# Circuit_primaire.net
KiCad netlist of a schematic drawn in Altium Designer
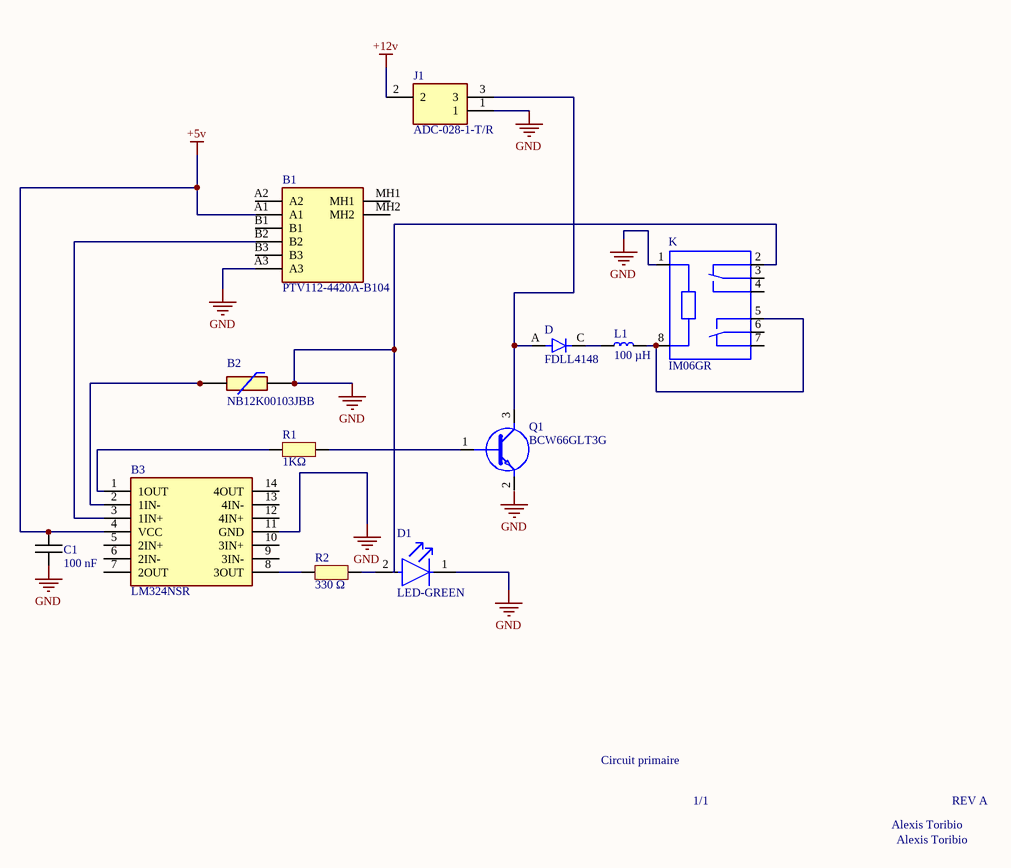
[diagram p0: Circuit primaire.SchDoc]

(export (version "E")
  (design (tool "Eeschema 10.0.6"))
  (components
    (comp (ref "B1")
      (value "PTV112-4420A-B104")
      (footprint "PTV1124420AB104")
      (description "Potentiometers PANEL CONTROL 100kOhm")
      (fields (field (name "MOUSER PART NUMBER") "652-PTV1124420AB104"))
      (libsource (lib "Schlib1") (part "PTV112-4420A-B104"))
    )
    (comp (ref "B2")
      (value "NB12K00103JBB")
      (footprint "RESC2212X50N")
      (description "NTC SMD Thermistor, NB12K, 10K, 5% AVX 10k 0805 Protection NTC Thermistor, 5s, 2 x 1.25 x 1.3mm")
      (fields (field (name "MOUSER PART NUMBER") "581-NB12K00103JBB"))
      (libsource (lib "Schlib1") (part "NB12K00103JBB"))
    )
    (comp (ref "B3")
      (value "LM324NSR")
      (footprint "SOIC127P780X200-14N")
      (description "Quadruple Operational Amplifier")
      (fields (field (name "MOUSER PART NUMBER") "595-LM324NSR"))
      (libsource (lib "Schlib1") (part "LM324NSR"))
    )
    (comp (ref "C1")
      (value "100 nF")
      (footprint "CAPC1005X06N")
      (libsource (lib "Schlib1") (part "Capacitor"))
    )
    (comp (ref "D")
      (value "FDLL4148")
      (footprint "DIOMELF3414N")
      (description "Diode Standard 100V 200mA Surface Mount SOD-80")
      (fields (field (name "MF") "ON Semiconductor") (field (name "DIGI-KEY_PART_NUMBER") "FDLL4148CT-ND"))
      (libsource (lib "Schlib1") (part "FDLL4148"))
    )
    (comp (ref "D1")
      (value "LED-GREEN")
      (footprint "SMD-1608-LED")
      (description "LED GREEN CLEAR CHIP SMD LTST-C190GKT")
      (fields (field (name "VOLTAGE") "2V"))
      (libsource (lib "Schlib1") (part "LED-GREEN"))
    )
    (comp (ref "J1")
      (value "ADC-028-1-T/R")
      (footprint "PJ1021SMTTR")
      (description "Connecteurs d'alimentation continue DC POWER JACK 2MM PIN TYPE 028")
      (fields (field (name "MOUSER PART NUMBER") "737-ADC-028-1-T/R"))
      (libsource (lib "Schlib1") (part "ADC-028-1-T/R"))
    )
    (comp (ref "K")
      (value "IM06GR")
      (footprint "RELAY_IM06GR")
      (description "Electromechanical Relay 12VDC 1.029KOhm 2A DPDT _10x7.5x5.65_mm SMD Signal Relay")
      (fields (field (name "MF") "TE Connectivity"))
      (libsource (lib "Schlib1") (part "IM06GR"))
    )
    (comp (ref "L1") (value "100 µH") (footprint "LQPC1005X06N") (libsource (lib "Schlib1") (part "Bobine")))
    (comp (ref "Q1")
      (value "BCW66GLT3G")
      (footprint "SOT96P237X111-3N")
      (description "NPN Bipolar Transistor")
      (fields (field (name "MOUSER PART NUMBER") "863-BCW66GLT3G"))
      (libsource (lib "Schlib1") (part "BCW66GLT3G"))
    )
    (comp (ref "R1") (value "1KΩ") (footprint "RESC1005X06N") (libsource (lib "Schlib1") (part "Resistor")))
    (comp (ref "R2") (value "330 Ω") (footprint "RESC1005X06N") (libsource (lib "Schlib1") (part "Resistor")))
  )
  (nets
    (net (code "1") (name "+5v") (class "Default")
      (node (ref "B1") (pin "A1") (pinfunction "A1_A1") (pintype "passive"))
      (node (ref "B3") (pin "4") (pinfunction "VCC_4") (pintype "passive"))
      (node (ref "C1") (pin "2") (pinfunction "2_2") (pintype "passive"))
    )
    (net (code "2") (name "+12v") (class "Default")
      (node (ref "J1") (pin "2") (pinfunction "2_2") (pintype "passive"))
    )
    (net (code "3") (name "GND") (class "Default")
      (node (ref "B1") (pin "A3") (pinfunction "A3_A3") (pintype "passive"))
      (node (ref "B2") (pin "1") (pinfunction "1_1") (pintype "passive"))
      (node (ref "B3") (pin "11") (pinfunction "GND_11") (pintype "passive"))
      (node (ref "C1") (pin "1") (pinfunction "1_1") (pintype "passive"))
      (node (ref "D1") (pin "1") (pinfunction "C_1") (pintype "passive"))
      (node (ref "J1") (pin "1") (pinfunction "1_1") (pintype "passive"))
      (node (ref "K") (pin "1") (pinfunction "1_1") (pintype "passive"))
      (node (ref "K") (pin "2") (pinfunction "2_2") (pintype "passive"))
    )
    (net (code "4") (name "Net-(B3-1IN+)") (class "Default")
      (node (ref "B1") (pin "B2") (pinfunction "B2_B2") (pintype "passive"))
      (node (ref "B3") (pin "3") (pinfunction "1IN+_3") (pintype "passive"))
    )
    (net (code "5") (name "Net-(B3-1IN-)") (class "Default")
      (node (ref "B2") (pin "2") (pinfunction "2_2") (pintype "passive"))
      (node (ref "B3") (pin "2") (pinfunction "1IN-_2") (pintype "passive"))
    )
    (net (code "6") (name "Net-(B3-1OUT)") (class "Default")
      (node (ref "B3") (pin "1") (pinfunction "1OUT_1") (pintype "passive"))
      (node (ref "R1") (pin "1") (pinfunction "1_1") (pintype "passive"))
    )
    (net (code "7") (name "Net-(B3-3OUT)") (class "Default")
      (node (ref "B3") (pin "8") (pinfunction "3OUT_8") (pintype "passive"))
      (node (ref "R2") (pin "1") (pinfunction "1_1") (pintype "passive"))
    )
    (net (code "8") (name "Net-(D-PadC)") (class "Default")
      (node (ref "D") (pin "C") (pinfunction "C_C") (pintype "passive"))
      (node (ref "L1") (pin "1") (pinfunction "1_1") (pintype "passive"))
    )
    (net (code "9") (name "Net-(D1-A)") (class "Default")
      (node (ref "D1") (pin "2") (pinfunction "A_2") (pintype "passive"))
      (node (ref "R2") (pin "2") (pinfunction "2_2") (pintype "passive"))
    )
    (net (code "10") (name "Net-(K-Pad5)") (class "Default")
      (node (ref "K") (pin "5") (pinfunction "5_5") (pintype "passive"))
      (node (ref "K") (pin "8") (pinfunction "8_8") (pintype "passive"))
      (node (ref "L1") (pin "2") (pinfunction "2_2") (pintype "passive"))
    )
    (net (code "11") (name "Net-(Q1-B)") (class "Default")
      (node (ref "Q1") (pin "1") (pinfunction "B_1") (pintype "passive"))
      (node (ref "R1") (pin "2") (pinfunction "2_2") (pintype "passive"))
    )
    (net (code "12") (name "Net-(Q1-C)") (class "Default")
      (node (ref "D") (pin "A") (pinfunction "A_A") (pintype "passive"))
      (node (ref "J1") (pin "3") (pinfunction "3_3") (pintype "passive"))
      (node (ref "Q1") (pin "3") (pinfunction "C_3") (pintype "passive"))
    )
    (net (code "13") (name "unconnected-(B1-PadA2)") (class "Default")
      (node (ref "B1") (pin "A2") (pinfunction "A2_A2") (pintype "passive"))
    )
    (net (code "14") (name "unconnected-(B1-PadB1)") (class "Default")
      (node (ref "B1") (pin "B1") (pinfunction "B1_B1") (pintype "passive"))
    )
    (net (code "15") (name "unconnected-(B1-PadB3)") (class "Default")
      (node (ref "B1") (pin "B3") (pinfunction "B3_B3") (pintype "passive"))
    )
    (net (code "16") (name "unconnected-(B1-PadMH1)") (class "Default")
      (node (ref "B1") (pin "MH1") (pinfunction "MH1_MH1") (pintype "passive"))
    )
    (net (code "17") (name "unconnected-(B1-PadMH2)") (class "Default")
      (node (ref "B1") (pin "MH2") (pinfunction "MH2_MH2") (pintype "passive"))
    )
    (net (code "18") (name "unconnected-(B3-2IN+-Pad5)") (class "Default")
      (node (ref "B3") (pin "5") (pinfunction "2IN+_5") (pintype "passive"))
    )
    (net (code "19") (name "unconnected-(B3-2IN--Pad6)") (class "Default")
      (node (ref "B3") (pin "6") (pinfunction "2IN-_6") (pintype "passive"))
    )
    (net (code "20") (name "unconnected-(B3-2OUT-Pad7)") (class "Default")
      (node (ref "B3") (pin "7") (pinfunction "2OUT_7") (pintype "passive"))
    )
    (net (code "21") (name "unconnected-(B3-3IN+-Pad10)") (class "Default")
      (node (ref "B3") (pin "10") (pinfunction "3IN+_10") (pintype "passive"))
    )
    (net (code "22") (name "unconnected-(B3-3IN--Pad9)") (class "Default")
      (node (ref "B3") (pin "9") (pinfunction "3IN-_9") (pintype "passive"))
    )
    (net (code "23") (name "unconnected-(B3-4IN+-Pad12)") (class "Default")
      (node (ref "B3") (pin "12") (pinfunction "4IN+_12") (pintype "passive"))
    )
    (net (code "24") (name "unconnected-(B3-4IN--Pad13)") (class "Default")
      (node (ref "B3") (pin "13") (pinfunction "4IN-_13") (pintype "passive"))
    )
    (net (code "25") (name "unconnected-(B3-4OUT-Pad14)") (class "Default")
      (node (ref "B3") (pin "14") (pinfunction "4OUT_14") (pintype "passive"))
    )
    (net (code "26") (name "unconnected-(K-Pad3)") (class "Default")
      (node (ref "K") (pin "3") (pinfunction "3_3") (pintype "passive"))
    )
    (net (code "27") (name "unconnected-(K-Pad4)") (class "Default")
      (node (ref "K") (pin "4") (pinfunction "4_4") (pintype "passive"))
    )
    (net (code "28") (name "unconnected-(K-Pad6)") (class "Default")
      (node (ref "K") (pin "6") (pinfunction "6_6") (pintype "passive"))
    )
    (net (code "29") (name "unconnected-(K-Pad7)") (class "Default")
      (node (ref "K") (pin "7") (pinfunction "7_7") (pintype "passive"))
    )
    (net (code "30") (name "unconnected-(Q1-E-Pad2)") (class "Default")
      (node (ref "Q1") (pin "2") (pinfunction "E_2") (pintype "passive"))
    )
  )
)
